# BiodataFeather_ThroughHole_005.net
KiCad netlist of a schematic drawn in EAGLE
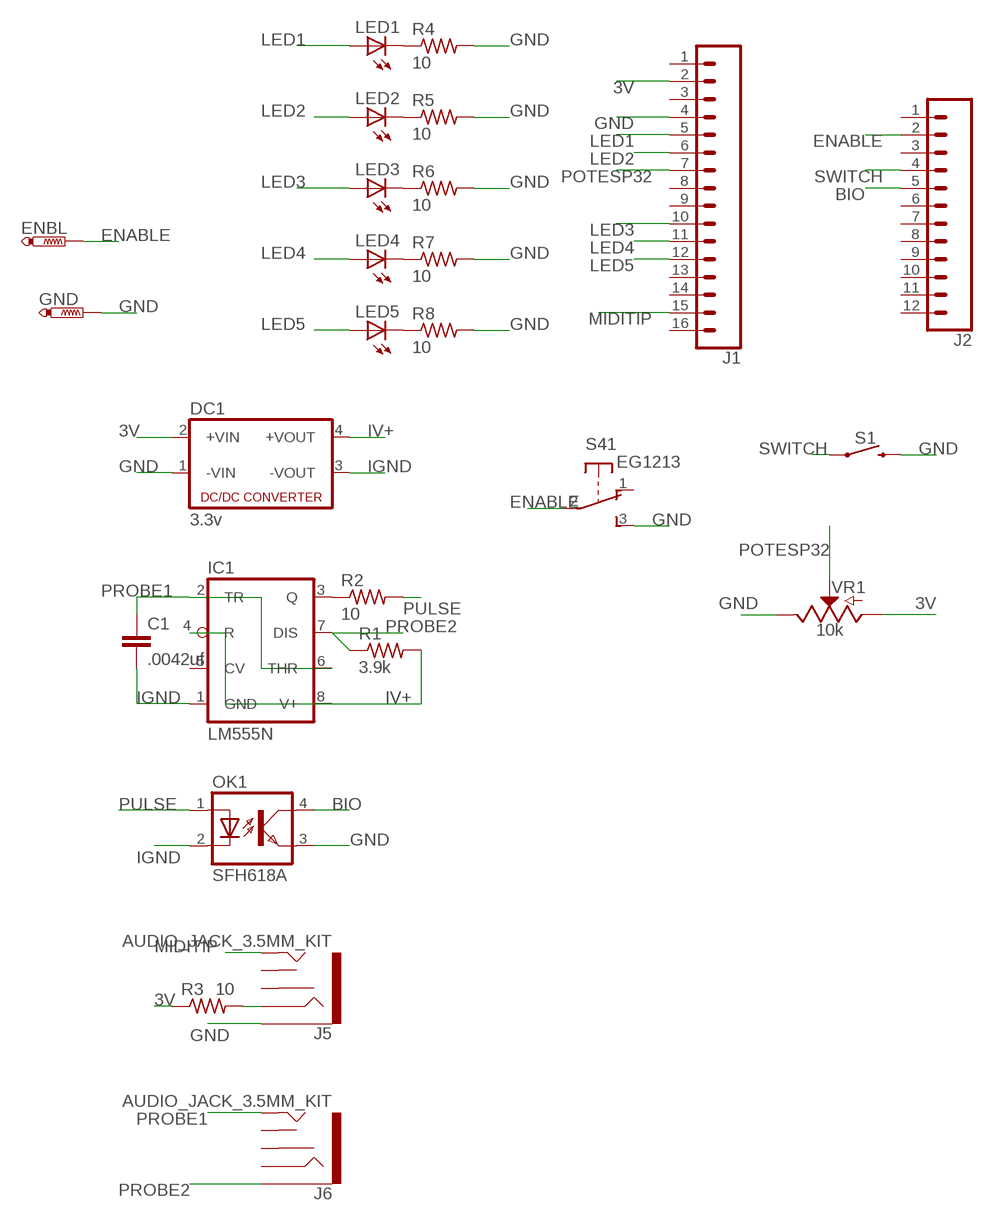
[diagram p0: schematic, sheet 1]

(export (version "E")
  (design (tool "Eeschema 10.0.6"))
  (components
    (comp (ref "C1")
      (value ".0042uf")
      (footprint "eagle-import:C2.5-2")
      (libsource (lib "eagle-import") (part "C2.5/2"))
    )
    (comp (ref "DC1")
      (value "3.3v")
      (footprint "eagle-import:NME")
      (fields (field (name "MF") "C & D TECHNOLOGIES, INC") (field (name "MPN") "NME1205D"))
      (libsource (lib "eagle-import") (part "NME"))
    )
    (comp (ref "ENBL")
      (value "PTR1TP20R")
      (footprint "eagle-import:TP20R")
      (libsource (lib "eagle-import") (part "PTR1TP20R"))
    )
    (comp (ref "GND")
      (value "PTR1TP20SQ")
      (footprint "eagle-import:TP20SQ")
      (libsource (lib "eagle-import") (part "PTR1TP20SQ"))
    )
    (comp (ref "IC1")
      (value "LM555N")
      (footprint "eagle-import:DIL08")
      (libsource (lib "eagle-import") (part "555NLM"))
    )
    (comp (ref "J1")
      (value "CONN_161X16_NO_SILK")
      (footprint "eagle-import:1X16_NO_SILK")
      (libsource (lib "eagle-import") (part "CONN_161X16_NO_SILK"))
    )
    (comp (ref "J2")
      (value "CONN_12NO_SILK")
      (footprint "eagle-import:1X12_NO_SILK")
      (libsource (lib "eagle-import") (part "CONN_12NO_SILK"))
    )
    (comp (ref "J5")
      (value "AUDIO_JACK_3.5MM_KIT")
      (footprint "eagle-import:AUDIO-JACK-KIT")
      (libsource (lib "eagle-import") (part "AUDIO_JACK_3.5MM_KIT"))
    )
    (comp (ref "J6")
      (value "AUDIO_JACK_3.5MM_KIT")
      (footprint "eagle-import:AUDIO-JACK-KIT")
      (libsource (lib "eagle-import") (part "AUDIO_JACK_3.5MM_KIT"))
    )
    (comp (ref "LED1")
      (value "LED5MM")
      (footprint "eagle-import:LED5MM")
      (libsource (lib "eagle-import") (part "LED5MM"))
    )
    (comp (ref "LED2")
      (value "LED5MM")
      (footprint "eagle-import:LED5MM")
      (libsource (lib "eagle-import") (part "LED5MM"))
    )
    (comp (ref "LED3")
      (value "LED5MM")
      (footprint "eagle-import:LED5MM")
      (libsource (lib "eagle-import") (part "LED5MM"))
    )
    (comp (ref "LED4")
      (value "LED5MM")
      (footprint "eagle-import:LED5MM")
      (libsource (lib "eagle-import") (part "LED5MM"))
    )
    (comp (ref "LED5")
      (value "LED5MM")
      (footprint "eagle-import:LED5MM")
      (libsource (lib "eagle-import") (part "LED5MM"))
    )
    (comp (ref "OK1")
      (value "SFH618A")
      (footprint "eagle-import:DIP4")
      (fields (field (name "MF") "VISHAY/TELEFUNKEN") (field (name "MPN") "SFH618A-5"))
      (libsource (lib "eagle-import") (part "SFH618?A-5"))
    )
    (comp (ref "R1")
      (value "3.9k")
      (footprint "eagle-import:0204V")
      (libsource (lib "eagle-import") (part "R-US_0204/2V"))
    )
    (comp (ref "R2")
      (value "10")
      (footprint "eagle-import:0204V")
      (libsource (lib "eagle-import") (part "R-US_0204/2V"))
    )
    (comp (ref "R3")
      (value "10")
      (footprint "eagle-import:0204V")
      (libsource (lib "eagle-import") (part "R-US_0204/2V"))
    )
    (comp (ref "R4")
      (value "10")
      (footprint "eagle-import:0204V")
      (libsource (lib "eagle-import") (part "R-US_0204/2V"))
    )
    (comp (ref "R5")
      (value "10")
      (footprint "eagle-import:0204V")
      (libsource (lib "eagle-import") (part "R-US_0204/2V"))
    )
    (comp (ref "R6")
      (value "10")
      (footprint "eagle-import:0204V")
      (libsource (lib "eagle-import") (part "R-US_0204/2V"))
    )
    (comp (ref "R7")
      (value "10")
      (footprint "eagle-import:0204V")
      (libsource (lib "eagle-import") (part "R-US_0204/2V"))
    )
    (comp (ref "R8")
      (value "10")
      (footprint "eagle-import:0204V")
      (libsource (lib "eagle-import") (part "R-US_0204/2V"))
    )
    (comp (ref "S1")
      (value "MOMENTARY-SWITCH-SPST-PTH-6.0MM")
      (footprint "eagle-import:TACTILE_SWITCH_PTH_6.0MM")
      (libsource (lib "eagle-import") (part "MOMENTARY-SWITCH-SPST-PTH-6.0MM"))
    )
    (comp (ref "S4")
      (value "EG1213")
      (footprint "eagle-import:EG1213")
      (libsource (lib "eagle-import") (part "EG1213"))
    )
    (comp (ref "VR1")
      (value "10k")
      (footprint "eagle-import:POT-PTH-ALPS-KIT")
      (libsource (lib "eagle-import") (part "POTENTIOMETER-PTH-9MM-1/20W-20%-KIT"))
    )
  )
  (nets
    (net (code "1") (name "/3V") (class "Default")
      (node (ref "DC1") (pin "2") (pinfunction "+VIN_2") (pintype "passive"))
      (node (ref "J1") (pin "2") (pinfunction "2_2") (pintype "passive"))
      (node (ref "R3") (pin "1") (pinfunction "1_1") (pintype "passive"))
      (node (ref "VR1") (pin "P$3") (pinfunction "A_P$3") (pintype "passive"))
    )
    (net (code "2") (name "/BIO") (class "Default")
      (node (ref "J2") (pin "5") (pinfunction "5_5") (pintype "passive"))
      (node (ref "OK1") (pin "4") (pinfunction "COL_4") (pintype "passive"))
    )
    (net (code "3") (name "/ENABLE") (class "Default")
      (node (ref "ENBL") (pin "TP") (pinfunction "TP_TP") (pintype "input"))
      (node (ref "J2") (pin "2") (pinfunction "2_2") (pintype "passive"))
      (node (ref "S4") (pin "2") (pinfunction "P_2") (pintype "passive"))
    )
    (net (code "4") (name "/GND") (class "Default")
      (node (ref "DC1") (pin "1") (pinfunction "-VIN_1") (pintype "passive"))
      (node (ref "GND") (pin "TP") (pinfunction "TP_TP") (pintype "input"))
      (node (ref "J1") (pin "4") (pinfunction "4_4") (pintype "passive"))
      (node (ref "J5") (pin "SLEEVE") (pinfunction "SLEEVE_SLEEVE") (pintype "bidirectional"))
      (node (ref "OK1") (pin "3") (pinfunction "EMIT_3") (pintype "passive"))
      (node (ref "R4") (pin "2") (pinfunction "2_2") (pintype "passive"))
      (node (ref "R5") (pin "2") (pinfunction "2_2") (pintype "passive"))
      (node (ref "R6") (pin "2") (pinfunction "2_2") (pintype "passive"))
      (node (ref "R7") (pin "2") (pinfunction "2_2") (pintype "passive"))
      (node (ref "R8") (pin "2") (pinfunction "2_2") (pintype "passive"))
      (node (ref "S1") (pin "3") (pinfunction "2_3") (pintype "passive"))
      (node (ref "S4") (pin "3") (pinfunction "S_3") (pintype "passive"))
      (node (ref "VR1") (pin "P$1") (pinfunction "E_P$1") (pintype "passive"))
    )
    (net (code "5") (name "/IGND") (class "Default")
      (node (ref "C1") (pin "2") (pinfunction "2_2") (pintype "passive"))
      (node (ref "DC1") (pin "3") (pinfunction "-VOUT_3") (pintype "passive"))
      (node (ref "IC1") (pin "1") (pinfunction "GND_1") (pintype "power_in"))
      (node (ref "OK1") (pin "2") (pinfunction "C_2") (pintype "passive"))
    )
    (net (code "6") (name "/IV+") (class "Default")
      (node (ref "DC1") (pin "4") (pinfunction "+VOUT_4") (pintype "passive"))
      (node (ref "IC1") (pin "4") (pinfunction "R_4") (pintype "input"))
      (node (ref "IC1") (pin "8") (pinfunction "V+_8") (pintype "power_in"))
      (node (ref "R1") (pin "2") (pinfunction "2_2") (pintype "passive"))
    )
    (net (code "7") (name "/LED1") (class "Default")
      (node (ref "J1") (pin "5") (pinfunction "5_5") (pintype "passive"))
      (node (ref "LED1") (pin "A") (pinfunction "A_A") (pintype "passive"))
    )
    (net (code "8") (name "/LED2") (class "Default")
      (node (ref "J1") (pin "6") (pinfunction "6_6") (pintype "passive"))
      (node (ref "LED2") (pin "A") (pinfunction "A_A") (pintype "passive"))
    )
    (net (code "9") (name "/LED3") (class "Default")
      (node (ref "J1") (pin "10") (pinfunction "10_10") (pintype "passive"))
      (node (ref "LED3") (pin "A") (pinfunction "A_A") (pintype "passive"))
    )
    (net (code "10") (name "/LED4") (class "Default")
      (node (ref "J1") (pin "11") (pinfunction "11_11") (pintype "passive"))
      (node (ref "LED4") (pin "A") (pinfunction "A_A") (pintype "passive"))
    )
    (net (code "11") (name "/LED5") (class "Default")
      (node (ref "J1") (pin "12") (pinfunction "12_12") (pintype "passive"))
      (node (ref "LED5") (pin "A") (pinfunction "A_A") (pintype "passive"))
    )
    (net (code "12") (name "/MIDITIP") (class "Default")
      (node (ref "J1") (pin "15") (pinfunction "15_15") (pintype "passive"))
      (node (ref "J5") (pin "TIP") (pinfunction "TIP_TIP") (pintype "bidirectional"))
    )
    (net (code "13") (name "/POTESP32") (class "Default")
      (node (ref "J1") (pin "7") (pinfunction "7_7") (pintype "passive"))
      (node (ref "VR1") (pin "P$2") (pinfunction "S_P$2") (pintype "passive"))
    )
    (net (code "14") (name "/PROBE1") (class "Default")
      (node (ref "C1") (pin "1") (pinfunction "1_1") (pintype "passive"))
      (node (ref "IC1") (pin "2") (pinfunction "TR_2") (pintype "input"))
      (node (ref "IC1") (pin "6") (pinfunction "THR_6") (pintype "input"))
      (node (ref "J6") (pin "TIP") (pinfunction "TIP_TIP") (pintype "bidirectional"))
    )
    (net (code "15") (name "/PROBE2") (class "Default")
      (node (ref "IC1") (pin "7") (pinfunction "DIS_7") (pintype "input"))
      (node (ref "J6") (pin "SLEEVE") (pinfunction "SLEEVE_SLEEVE") (pintype "bidirectional"))
      (node (ref "R1") (pin "1") (pinfunction "1_1") (pintype "passive"))
    )
    (net (code "16") (name "/PULSE") (class "Default")
      (node (ref "OK1") (pin "1") (pinfunction "A_1") (pintype "passive"))
      (node (ref "R2") (pin "2") (pinfunction "2_2") (pintype "passive"))
    )
    (net (code "17") (name "/SWITCH") (class "Default")
      (node (ref "J2") (pin "4") (pinfunction "4_4") (pintype "passive"))
      (node (ref "S1") (pin "1") (pinfunction "1_1") (pintype "passive"))
    )
    (net (code "18") (name "Net-(IC1-Q)") (class "Default")
      (node (ref "IC1") (pin "3") (pinfunction "Q_3") (pintype "output"))
      (node (ref "R2") (pin "1") (pinfunction "1_1") (pintype "passive"))
    )
    (net (code "19") (name "Net-(J5-PadRING)") (class "Default")
      (node (ref "J5") (pin "RING") (pinfunction "RING_RING") (pintype "bidirectional"))
      (node (ref "R3") (pin "2") (pinfunction "2_2") (pintype "passive"))
    )
    (net (code "20") (name "Net-(LED1-C)") (class "Default")
      (node (ref "LED1") (pin "K") (pinfunction "C_K") (pintype "passive"))
      (node (ref "R4") (pin "1") (pinfunction "1_1") (pintype "passive"))
    )
    (net (code "21") (name "Net-(LED2-C)") (class "Default")
      (node (ref "LED2") (pin "K") (pinfunction "C_K") (pintype "passive"))
      (node (ref "R5") (pin "1") (pinfunction "1_1") (pintype "passive"))
    )
    (net (code "22") (name "Net-(LED3-C)") (class "Default")
      (node (ref "LED3") (pin "K") (pinfunction "C_K") (pintype "passive"))
      (node (ref "R6") (pin "1") (pinfunction "1_1") (pintype "passive"))
    )
    (net (code "23") (name "Net-(LED4-C)") (class "Default")
      (node (ref "LED4") (pin "K") (pinfunction "C_K") (pintype "passive"))
      (node (ref "R7") (pin "1") (pinfunction "1_1") (pintype "passive"))
    )
    (net (code "24") (name "Net-(LED5-C)") (class "Default")
      (node (ref "LED5") (pin "K") (pinfunction "C_K") (pintype "passive"))
      (node (ref "R8") (pin "1") (pinfunction "1_1") (pintype "passive"))
    )
    (net (code "25") (name "unconnected-(IC1-CV-Pad5)") (class "Default")
      (node (ref "IC1") (pin "5") (pinfunction "CV_5") (pintype "input"))
    )
    (net (code "26") (name "unconnected-(J1-Pad1)") (class "Default")
      (node (ref "J1") (pin "1") (pinfunction "1_1") (pintype "passive"))
    )
    (net (code "27") (name "unconnected-(J1-Pad3)") (class "Default")
      (node (ref "J1") (pin "3") (pinfunction "3_3") (pintype "passive"))
    )
    (net (code "28") (name "unconnected-(J1-Pad8)") (class "Default")
      (node (ref "J1") (pin "8") (pinfunction "8_8") (pintype "passive"))
    )
    (net (code "29") (name "unconnected-(J1-Pad9)") (class "Default")
      (node (ref "J1") (pin "9") (pinfunction "9_9") (pintype "passive"))
    )
    (net (code "30") (name "unconnected-(J1-Pad13)") (class "Default")
      (node (ref "J1") (pin "13") (pinfunction "13_13") (pintype "passive"))
    )
    (net (code "31") (name "unconnected-(J1-Pad14)") (class "Default")
      (node (ref "J1") (pin "14") (pinfunction "14_14") (pintype "passive"))
    )
    (net (code "32") (name "unconnected-(J1-Pad16)") (class "Default")
      (node (ref "J1") (pin "16") (pinfunction "16_16") (pintype "passive"))
    )
    (net (code "33") (name "unconnected-(J2-Pad1)") (class "Default")
      (node (ref "J2") (pin "1") (pinfunction "1_1") (pintype "passive"))
    )
    (net (code "34") (name "unconnected-(J2-Pad3)") (class "Default")
      (node (ref "J2") (pin "3") (pinfunction "3_3") (pintype "passive"))
    )
    (net (code "35") (name "unconnected-(J2-Pad6)") (class "Default")
      (node (ref "J2") (pin "6") (pinfunction "6_6") (pintype "passive"))
    )
    (net (code "36") (name "unconnected-(J2-Pad7)") (class "Default")
      (node (ref "J2") (pin "7") (pinfunction "7_7") (pintype "passive"))
    )
    (net (code "37") (name "unconnected-(J2-Pad8)") (class "Default")
      (node (ref "J2") (pin "8") (pinfunction "8_8") (pintype "passive"))
    )
    (net (code "38") (name "unconnected-(J2-Pad9)") (class "Default")
      (node (ref "J2") (pin "9") (pinfunction "9_9") (pintype "passive"))
    )
    (net (code "39") (name "unconnected-(J2-Pad10)") (class "Default")
      (node (ref "J2") (pin "10") (pinfunction "10_10") (pintype "passive"))
    )
    (net (code "40") (name "unconnected-(J2-Pad11)") (class "Default")
      (node (ref "J2") (pin "11") (pinfunction "11_11") (pintype "passive"))
    )
    (net (code "41") (name "unconnected-(J2-Pad12)") (class "Default")
      (node (ref "J2") (pin "12") (pinfunction "12_12") (pintype "passive"))
    )
    (net (code "42") (name "unconnected-(J5-PadRSH)") (class "Default")
      (node (ref "J5") (pin "RSH") (pinfunction "RSH_RSH") (pintype "bidirectional"))
    )
    (net (code "43") (name "unconnected-(J5-PadTSH)") (class "Default")
      (node (ref "J5") (pin "TSH") (pinfunction "TSH_TSH") (pintype "bidirectional"))
    )
    (net (code "44") (name "unconnected-(J6-PadRING)") (class "Default")
      (node (ref "J6") (pin "RING") (pinfunction "RING_RING") (pintype "bidirectional"))
    )
    (net (code "45") (name "unconnected-(J6-PadRSH)") (class "Default")
      (node (ref "J6") (pin "RSH") (pinfunction "RSH_RSH") (pintype "bidirectional"))
    )
    (net (code "46") (name "unconnected-(J6-PadTSH)") (class "Default")
      (node (ref "J6") (pin "TSH") (pinfunction "TSH_TSH") (pintype "bidirectional"))
    )
    (net (code "47") (name "unconnected-(S4A-O-Pad1)") (class "Default")
      (node (ref "S4") (pin "1") (pinfunction "O_1") (pintype "passive"))
    )
  )
)
